# TEMP.net
KiCad netlist of a schematic drawn in Altium Designer
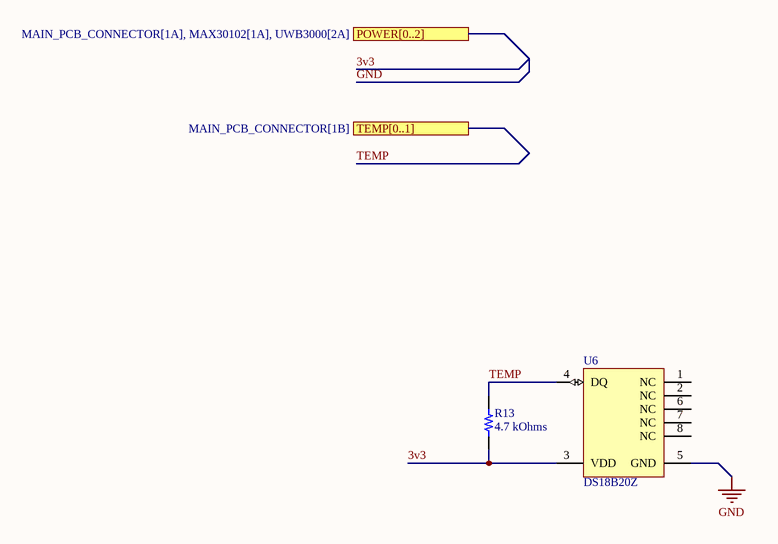
[diagram p0: TEMP.SchDoc]

(export (version "E")
  (design (tool "Eeschema 10.0.6"))
  (components
    (comp (ref "R13")
      (value "4.7 kOhms")
      (footprint "RES 0402_1005")
      (description "RES SMD 4.7K OHM 0.5% 1/16W 0402")
      (fields (field (name "PART NUMBER") "RR0510P-472-D") (field (name "TOLERANCE") "±0.5%"))
      (libsource (lib "Celestial Altium Library - altium_library") (part "Resistor"))
    )
    (comp (ref "U6")
      (value "DS18B20Z")
      (footprint "MAXM-S8-2_N")
      (description "High-Precision 1-Wire Digital Thermometer, -55 to 125 degC, 8-Pin SOIC (S8-2)")
      (fields
        (field (name "GENERIC PART NUMBER") "DS18B20")
        (field (name "MANUFACTURER") "Analog Devices Inc./Maxim Integrated")
      )
      (libsource (lib "Altium Content Vault") (part "DS18B20-S8-2"))
    )
  )
  (nets
    (net (code "6") (name "/3v3") (class "Default")
      (node (ref "R13") (pin "1") (pinfunction "1_1") (pintype "passive"))
      (node (ref "U6") (pin "3") (pinfunction "VDD_3") (pintype "power_in"))
    )
    (net (code "8") (name "/TEMP") (class "Default")
      (node (ref "R13") (pin "2") (pinfunction "2_2") (pintype "passive"))
      (node (ref "U6") (pin "4") (pinfunction "DQ_4") (pintype "bidirectional"))
    )
    (net (code "10") (name "GND") (class "Default")
      (node (ref "U6") (pin "5") (pinfunction "GND_5") (pintype "power_in"))
    )
    (net (code "11") (name "unconnected-(U6-NC-Pad1)") (class "Default")
      (node (ref "U6") (pin "1") (pinfunction "NC_1") (pintype "passive"))
    )
    (net (code "12") (name "unconnected-(U6-NC-Pad2)") (class "Default")
      (node (ref "U6") (pin "2") (pinfunction "NC_2") (pintype "passive"))
    )
    (net (code "13") (name "unconnected-(U6-NC-Pad6)") (class "Default")
      (node (ref "U6") (pin "6") (pinfunction "NC_6") (pintype "passive"))
    )
    (net (code "14") (name "unconnected-(U6-NC-Pad7)") (class "Default")
      (node (ref "U6") (pin "7") (pinfunction "NC_7") (pintype "passive"))
    )
    (net (code "15") (name "unconnected-(U6-NC-Pad8)") (class "Default")
      (node (ref "U6") (pin "8") (pinfunction "NC_8") (pintype "passive"))
    )
  )
)
